# B34.net
KiCad netlist of a schematic drawn in Altium Designer
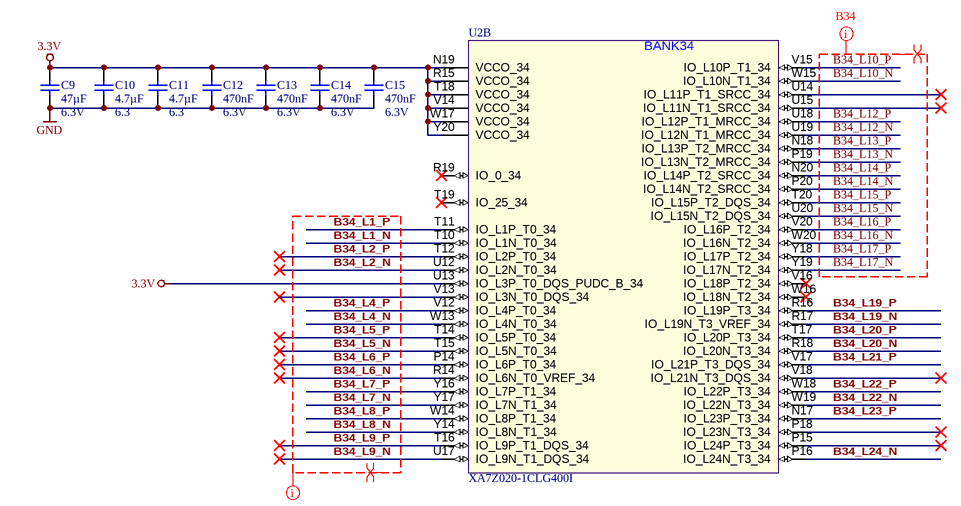
[diagram p0: B34.SchDoc]

(export (version "E")
  (design (tool "Eeschema 10.0.6"))
  (components
    (comp (ref "C9")
      (value "47µF")
      (footprint "CAPC3216X180N")
      (description "KON 47µF 6.3V  X5R SMD 20%")
      (fields (field (name "VOLTAGE") "6.3V") (field (name "TOLERANCE") "20%"))
      (libsource (lib "TE") (part "CAP-NP"))
    )
    (comp (ref "C10")
      (value "4.7µF")
      (footprint "CAPC1005X60N")
      (description "KON 4.7µF 6.3V X5R SMD")
      (fields (field (name "VOLTAGE") "6.3"))
      (libsource (lib "TE") (part "CAP-NP"))
    )
    (comp (ref "C11")
      (value "4.7µF")
      (footprint "CAPC1005X60N")
      (description "KON 4.7µF 6.3V X5R SMD")
      (fields (field (name "VOLTAGE") "6.3"))
      (libsource (lib "TE") (part "CAP-NP"))
    )
    (comp (ref "C12")
      (value "470nF")
      (footprint "CAPC0603X33N")
      (description "KON 470nF X5R 6.3V SMD")
      (fields (field (name "VOLTAGE") "6.3V") (field (name "TOLERANCE") "20%"))
      (libsource (lib "TE") (part "CAP-NP"))
    )
    (comp (ref "C13")
      (value "470nF")
      (footprint "CAPC0603X33N")
      (description "KON 470nF X5R 6.3V SMD")
      (fields (field (name "VOLTAGE") "6.3V") (field (name "TOLERANCE") "20%"))
      (libsource (lib "TE") (part "CAP-NP"))
    )
    (comp (ref "C14")
      (value "470nF")
      (footprint "CAPC0603X33N")
      (description "KON 470nF X5R 6.3V SMD")
      (fields (field (name "VOLTAGE") "6.3V") (field (name "TOLERANCE") "20%"))
      (libsource (lib "TE") (part "CAP-NP"))
    )
    (comp (ref "C15")
      (value "470nF")
      (footprint "CAPC0603X33N")
      (description "KON 470nF X5R 6.3V SMD")
      (fields (field (name "VOLTAGE") "6.3V") (field (name "TOLERANCE") "20%"))
      (libsource (lib "TE") (part "CAP-NP"))
    )
    (comp (ref "U2")
      (value "XA7Z020-1CLG400I")
      (footprint "BGA400C80P20X20_1700X1700X160N")
      (libsource (lib "TE") (part "XC7Z020-2CLG400C"))
    )
  )
  (nets
    (net (code "1") (name "/B34_L1_N") (class "Default")
      (node (ref "U2") (pin "T10") (pinfunction "IO_L1N_T0_34_T10") (pintype "bidirectional"))
    )
    (net (code "2") (name "/B34_L1_P") (class "Default")
      (node (ref "U2") (pin "T11") (pinfunction "IO_L1P_T0_34_T11") (pintype "bidirectional"))
    )
    (net (code "3") (name "/B34_L2_N") (class "Default")
      (node (ref "U2") (pin "U12") (pinfunction "IO_L2N_T0_34_U12") (pintype "bidirectional+no_connect"))
    )
    (net (code "4") (name "/B34_L2_P") (class "Default")
      (node (ref "U2") (pin "T12") (pinfunction "IO_L2P_T0_34_T12") (pintype "bidirectional+no_connect"))
    )
    (net (code "5") (name "/B34_L4_N") (class "Default")
      (node (ref "U2") (pin "W13") (pinfunction "IO_L4N_T0_34_W13") (pintype "bidirectional"))
    )
    (net (code "6") (name "/B34_L4_P") (class "Default")
      (node (ref "U2") (pin "V12") (pinfunction "IO_L4P_T0_34_V12") (pintype "bidirectional"))
    )
    (net (code "7") (name "/B34_L5_N") (class "Default")
      (node (ref "U2") (pin "T15") (pinfunction "IO_L5N_T0_34_T15") (pintype "bidirectional+no_connect"))
    )
    (net (code "8") (name "/B34_L5_P") (class "Default")
      (node (ref "U2") (pin "T14") (pinfunction "IO_L5P_T0_34_T14") (pintype "bidirectional+no_connect"))
    )
    (net (code "9") (name "/B34_L6_N") (class "Default")
      (node (ref "U2") (pin "R14") (pinfunction "IO_L6N_T0_VREF_34_R14") (pintype "bidirectional+no_connect"))
    )
    (net (code "10") (name "/B34_L6_P") (class "Default")
      (node (ref "U2") (pin "P14") (pinfunction "IO_L6P_T0_34_P14") (pintype "bidirectional+no_connect"))
    )
    (net (code "11") (name "/B34_L7_N") (class "Default")
      (node (ref "U2") (pin "Y17") (pinfunction "IO_L7N_T1_34_Y17") (pintype "bidirectional"))
    )
    (net (code "12") (name "/B34_L7_P") (class "Default")
      (node (ref "U2") (pin "Y16") (pinfunction "IO_L7P_T1_34_Y16") (pintype "bidirectional"))
    )
    (net (code "13") (name "/B34_L8_N") (class "Default")
      (node (ref "U2") (pin "Y14") (pinfunction "IO_L8N_T1_34_Y14") (pintype "bidirectional"))
    )
    (net (code "14") (name "/B34_L8_P") (class "Default")
      (node (ref "U2") (pin "W14") (pinfunction "IO_L8P_T1_34_W14") (pintype "bidirectional"))
    )
    (net (code "15") (name "/B34_L9_N") (class "Default")
      (node (ref "U2") (pin "U17") (pinfunction "IO_L9N_T1_DQS_34_U17") (pintype "bidirectional+no_connect"))
    )
    (net (code "16") (name "/B34_L9_P") (class "Default")
      (node (ref "U2") (pin "T16") (pinfunction "IO_L9P_T1_DQS_34_T16") (pintype "bidirectional+no_connect"))
    )
    (net (code "17") (name "/B34_L10_N") (class "Default")
      (node (ref "U2") (pin "W15") (pinfunction "IO_L10N_T1_34_W15") (pintype "bidirectional"))
    )
    (net (code "18") (name "/B34_L10_P") (class "Default")
      (node (ref "U2") (pin "V15") (pinfunction "IO_L10P_T1_34_V15") (pintype "bidirectional"))
    )
    (net (code "19") (name "/B34_L12_N") (class "Default")
      (node (ref "U2") (pin "U19") (pinfunction "IO_L12N_T1_MRCC_34_U19") (pintype "bidirectional"))
    )
    (net (code "20") (name "/B34_L12_P") (class "Default")
      (node (ref "U2") (pin "U18") (pinfunction "IO_L12P_T1_MRCC_34_U18") (pintype "bidirectional"))
    )
    (net (code "21") (name "/B34_L13_N") (class "Default")
      (node (ref "U2") (pin "P19") (pinfunction "IO_L13N_T2_MRCC_34_P19") (pintype "bidirectional"))
    )
    (net (code "22") (name "/B34_L13_P") (class "Default")
      (node (ref "U2") (pin "N18") (pinfunction "IO_L13P_T2_MRCC_34_N18") (pintype "bidirectional"))
    )
    (net (code "23") (name "/B34_L14_N") (class "Default")
      (node (ref "U2") (pin "P20") (pinfunction "IO_L14N_T2_SRCC_34_P20") (pintype "bidirectional"))
    )
    (net (code "24") (name "/B34_L14_P") (class "Default")
      (node (ref "U2") (pin "N20") (pinfunction "IO_L14P_T2_SRCC_34_N20") (pintype "bidirectional"))
    )
    (net (code "25") (name "/B34_L15_N") (class "Default")
      (node (ref "U2") (pin "U20") (pinfunction "IO_L15N_T2_DQS_34_U20") (pintype "bidirectional"))
    )
    (net (code "26") (name "/B34_L15_P") (class "Default")
      (node (ref "U2") (pin "T20") (pinfunction "IO_L15P_T2_DQS_34_T20") (pintype "bidirectional"))
    )
    (net (code "27") (name "/B34_L16_N") (class "Default")
      (node (ref "U2") (pin "W20") (pinfunction "IO_L16N_T2_34_W20") (pintype "bidirectional"))
    )
    (net (code "28") (name "/B34_L16_P") (class "Default")
      (node (ref "U2") (pin "V20") (pinfunction "IO_L16P_T2_34_V20") (pintype "bidirectional"))
    )
    (net (code "29") (name "/B34_L17_N") (class "Default")
      (node (ref "U2") (pin "Y19") (pinfunction "IO_L17N_T2_34_Y19") (pintype "bidirectional"))
    )
    (net (code "30") (name "/B34_L17_P") (class "Default")
      (node (ref "U2") (pin "Y18") (pinfunction "IO_L17P_T2_34_Y18") (pintype "bidirectional"))
    )
    (net (code "31") (name "/B34_L19_N") (class "Default")
      (node (ref "U2") (pin "R17") (pinfunction "IO_L19N_T3_VREF_34_R17") (pintype "bidirectional"))
    )
    (net (code "32") (name "/B34_L19_P") (class "Default")
      (node (ref "U2") (pin "R16") (pinfunction "IO_L19P_T3_34_R16") (pintype "bidirectional"))
    )
    (net (code "33") (name "/B34_L20_N") (class "Default")
      (node (ref "U2") (pin "R18") (pinfunction "IO_L20N_T3_34_R18") (pintype "bidirectional"))
    )
    (net (code "34") (name "/B34_L20_P") (class "Default")
      (node (ref "U2") (pin "T17") (pinfunction "IO_L20P_T3_34_T17") (pintype "bidirectional"))
    )
    (net (code "35") (name "/B34_L21_P") (class "Default")
      (node (ref "U2") (pin "V17") (pinfunction "IO_L21P_T3_DQS_34_V17") (pintype "bidirectional"))
    )
    (net (code "36") (name "/B34_L22_N") (class "Default")
      (node (ref "U2") (pin "W19") (pinfunction "IO_L22N_T3_34_W19") (pintype "bidirectional"))
    )
    (net (code "37") (name "/B34_L22_P") (class "Default")
      (node (ref "U2") (pin "W18") (pinfunction "IO_L22P_T3_34_W18") (pintype "bidirectional"))
    )
    (net (code "38") (name "/B34_L23_P") (class "Default")
      (node (ref "U2") (pin "N17") (pinfunction "IO_L23P_T3_34_N17") (pintype "bidirectional"))
    )
    (net (code "39") (name "/B34_L24_N") (class "Default")
      (node (ref "U2") (pin "P16") (pinfunction "IO_L24N_T3_34_P16") (pintype "bidirectional"))
    )
    (net (code "40") (name "3.3V") (class "Default")
      (node (ref "C10") (pin "1") (pinfunction "1_1") (pintype "passive"))
      (node (ref "C11") (pin "1") (pinfunction "1_1") (pintype "passive"))
      (node (ref "C12") (pin "1") (pinfunction "1_1") (pintype "passive"))
      (node (ref "C13") (pin "1") (pinfunction "1_1") (pintype "passive"))
      (node (ref "C14") (pin "1") (pinfunction "1_1") (pintype "passive"))
      (node (ref "C15") (pin "1") (pinfunction "1_1") (pintype "passive"))
      (node (ref "C9") (pin "1") (pinfunction "1_1") (pintype "passive"))
      (node (ref "U2") (pin "N19") (pinfunction "VCCO_34_N19") (pintype "power_in"))
      (node (ref "U2") (pin "R15") (pinfunction "VCCO_34_R15") (pintype "power_in"))
      (node (ref "U2") (pin "T18") (pinfunction "VCCO_34_T18") (pintype "power_in"))
      (node (ref "U2") (pin "U13") (pinfunction "IO_L3P_T0_DQS_PUDC_B_34_U13") (pintype "bidirectional"))
      (node (ref "U2") (pin "V14") (pinfunction "VCCO_34_V14") (pintype "power_in"))
      (node (ref "U2") (pin "W17") (pinfunction "VCCO_34_W17") (pintype "power_in"))
      (node (ref "U2") (pin "Y20") (pinfunction "VCCO_34_Y20") (pintype "power_in"))
    )
    (net (code "41") (name "GND") (class "Default")
      (node (ref "C10") (pin "2") (pinfunction "2_2") (pintype "passive"))
      (node (ref "C11") (pin "2") (pinfunction "2_2") (pintype "passive"))
      (node (ref "C12") (pin "2") (pinfunction "2_2") (pintype "passive"))
      (node (ref "C13") (pin "2") (pinfunction "2_2") (pintype "passive"))
      (node (ref "C14") (pin "2") (pinfunction "2_2") (pintype "passive"))
      (node (ref "C15") (pin "2") (pinfunction "2_2") (pintype "passive"))
      (node (ref "C9") (pin "2") (pinfunction "2_2") (pintype "passive"))
    )
    (net (code "42") (name "unconnected-(U2B-IO_0_34-PadR19)") (class "Default")
      (node (ref "U2") (pin "R19") (pinfunction "IO_0_34_R19") (pintype "bidirectional+no_connect"))
    )
    (net (code "43") (name "unconnected-(U2B-IO_25_34-PadT19)") (class "Default")
      (node (ref "U2") (pin "T19") (pinfunction "IO_25_34_T19") (pintype "bidirectional+no_connect"))
    )
    (net (code "44") (name "unconnected-(U2B-IO_L3N_T0_DQS_34-PadV13)") (class "Default")
      (node (ref "U2") (pin "V13") (pinfunction "IO_L3N_T0_DQS_34_V13") (pintype "bidirectional+no_connect"))
    )
    (net (code "45") (name "unconnected-(U2B-IO_L11N_T1_SRCC_34-PadU15)") (class "Default")
      (node (ref "U2") (pin "U15") (pinfunction "IO_L11N_T1_SRCC_34_U15") (pintype "bidirectional+no_connect"))
    )
    (net (code "46") (name "unconnected-(U2B-IO_L11P_T1_SRCC_34-PadU14)") (class "Default")
      (node (ref "U2") (pin "U14") (pinfunction "IO_L11P_T1_SRCC_34_U14") (pintype "bidirectional+no_connect"))
    )
    (net (code "47") (name "unconnected-(U2B-IO_L18N_T2_34-PadW16)") (class "Default")
      (node (ref "U2") (pin "W16") (pinfunction "IO_L18N_T2_34_W16") (pintype "bidirectional+no_connect"))
    )
    (net (code "48") (name "unconnected-(U2B-IO_L18P_T2_34-PadV16)") (class "Default")
      (node (ref "U2") (pin "V16") (pinfunction "IO_L18P_T2_34_V16") (pintype "bidirectional+no_connect"))
    )
    (net (code "49") (name "unconnected-(U2B-IO_L21N_T3_DQS_34-PadV18)") (class "Default")
      (node (ref "U2") (pin "V18") (pinfunction "IO_L21N_T3_DQS_34_V18") (pintype "bidirectional+no_connect"))
    )
    (net (code "50") (name "unconnected-(U2B-IO_L23N_T3_34-PadP18)") (class "Default")
      (node (ref "U2") (pin "P18") (pinfunction "IO_L23N_T3_34_P18") (pintype "bidirectional+no_connect"))
    )
    (net (code "51") (name "unconnected-(U2B-IO_L24P_T3_34-PadP15)") (class "Default")
      (node (ref "U2") (pin "P15") (pinfunction "IO_L24P_T3_34_P15") (pintype "bidirectional+no_connect"))
    )
  )
)
